# PCB_3U_CamLink.net
KiCad netlist of a schematic drawn in Altium Designer
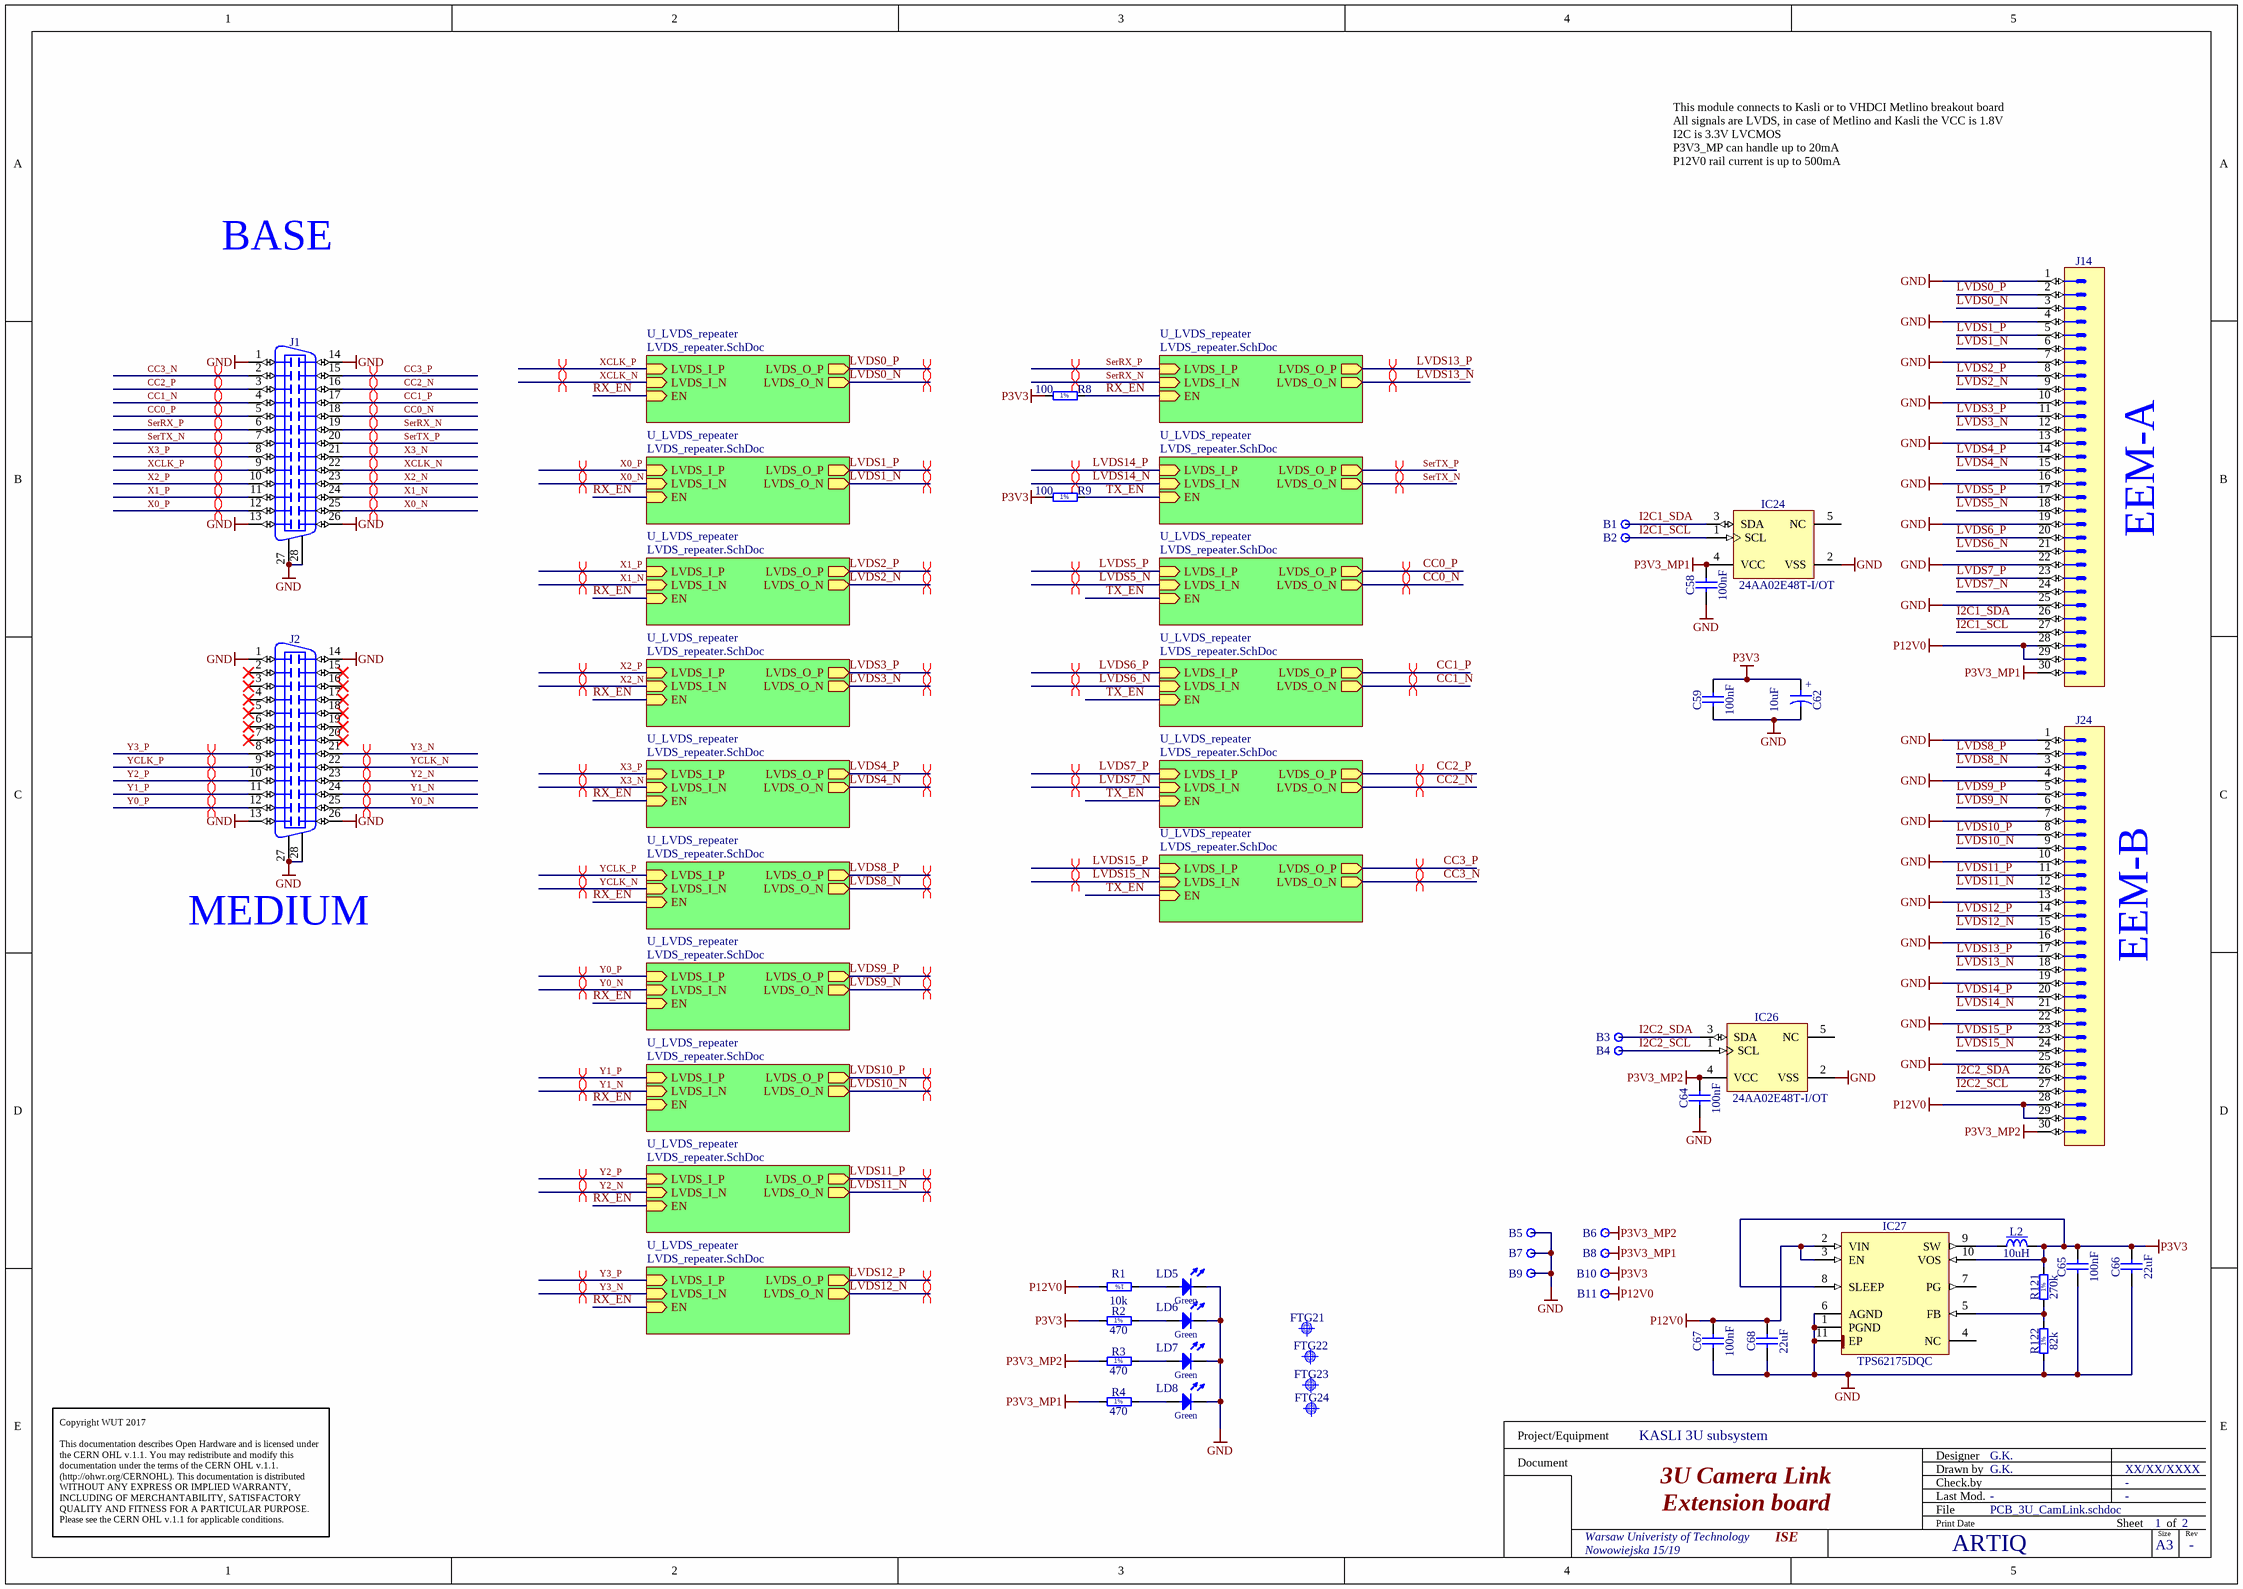
[diagram p0: PCB_3U_CamLink.schdoc]

(export (version "E")
  (design (tool "Eeschema 10.0.6"))
  (components
    (comp (ref "B1")
      (value "Plated Hole")
      (footprint "c130h60")
      (description "Single Terminal Socket")
      (fields (field (name "PART NUMBER") "PLATED_HOLE0.6_PAD1.3") (field (name "AUTHOR") "CERN DEM MR"))
      (libsource (lib "Eletro-mechanical") (part "Single Terminal Socket"))
    )
    (comp (ref "B2")
      (value "Plated Hole")
      (footprint "c130h60")
      (description "Single Terminal Socket")
      (fields (field (name "PART NUMBER") "PLATED_HOLE0.6_PAD1.3") (field (name "AUTHOR") "CERN DEM MR"))
      (libsource (lib "Eletro-mechanical") (part "Single Terminal Socket"))
    )
    (comp (ref "B3")
      (value "Plated Hole")
      (footprint "c130h60")
      (description "Single Terminal Socket")
      (fields (field (name "PART NUMBER") "PLATED_HOLE0.6_PAD1.3") (field (name "AUTHOR") "CERN DEM MR"))
      (libsource (lib "Eletro-mechanical") (part "Single Terminal Socket"))
    )
    (comp (ref "B4")
      (value "Plated Hole")
      (footprint "c130h60")
      (description "Single Terminal Socket")
      (fields (field (name "PART NUMBER") "PLATED_HOLE0.6_PAD1.3") (field (name "AUTHOR") "CERN DEM MR"))
      (libsource (lib "Eletro-mechanical") (part "Single Terminal Socket"))
    )
    (comp (ref "B5")
      (value "Plated Hole")
      (footprint "c130h60")
      (description "Single Terminal Socket")
      (fields (field (name "PART NUMBER") "PLATED_HOLE0.6_PAD1.3") (field (name "AUTHOR") "CERN DEM MR"))
      (libsource (lib "Eletro-mechanical") (part "Single Terminal Socket"))
    )
    (comp (ref "B6")
      (value "Plated Hole")
      (footprint "c130h60")
      (description "Single Terminal Socket")
      (fields (field (name "PART NUMBER") "PLATED_HOLE0.6_PAD1.3") (field (name "AUTHOR") "CERN DEM MR"))
      (libsource (lib "Eletro-mechanical") (part "Single Terminal Socket"))
    )
    (comp (ref "B7")
      (value "Plated Hole")
      (footprint "c130h60")
      (description "Single Terminal Socket")
      (fields (field (name "PART NUMBER") "PLATED_HOLE0.6_PAD1.3") (field (name "AUTHOR") "CERN DEM MR"))
      (libsource (lib "Eletro-mechanical") (part "Single Terminal Socket"))
    )
    (comp (ref "B8")
      (value "Plated Hole")
      (footprint "c130h60")
      (description "Single Terminal Socket")
      (fields (field (name "PART NUMBER") "PLATED_HOLE0.6_PAD1.3") (field (name "AUTHOR") "CERN DEM MR"))
      (libsource (lib "Eletro-mechanical") (part "Single Terminal Socket"))
    )
    (comp (ref "B9")
      (value "Plated Hole")
      (footprint "c130h60")
      (description "Single Terminal Socket")
      (fields (field (name "PART NUMBER") "PLATED_HOLE0.6_PAD1.3") (field (name "AUTHOR") "CERN DEM MR"))
      (libsource (lib "Eletro-mechanical") (part "Single Terminal Socket"))
    )
    (comp (ref "B10")
      (value "Plated Hole")
      (footprint "c130h60")
      (description "Single Terminal Socket")
      (fields (field (name "PART NUMBER") "PLATED_HOLE0.6_PAD1.3") (field (name "AUTHOR") "CERN DEM MR"))
      (libsource (lib "Eletro-mechanical") (part "Single Terminal Socket"))
    )
    (comp (ref "B11")
      (value "Plated Hole")
      (footprint "c130h60")
      (description "Single Terminal Socket")
      (fields (field (name "PART NUMBER") "PLATED_HOLE0.6_PAD1.3") (field (name "AUTHOR") "CERN DEM MR"))
      (libsource (lib "Eletro-mechanical") (part "Single Terminal Socket"))
    )
    (comp (ref "C58")
      (value "100nF")
      (footprint "CAPC1005X55N")
      (description "Non-polarised capacitor")
      (fields
        (field (name "PART NUMBER") "CC0402_100NF_16V_10%_X5R")
        (field (name "VOLTAGE") "16V")
        (field (name "AUTHOR") "CERN DEM JLC")
      )
      (libsource (lib "Capacitors") (part "Capacitor - non polarized"))
    )
    (comp (ref "C59")
      (value "100nF")
      (footprint "CAPC1005X55N")
      (description "Non-polarised capacitor")
      (fields
        (field (name "PART NUMBER") "CC0402_100NF_16V_10%_X5R")
        (field (name "VOLTAGE") "16V")
        (field (name "AUTHOR") "CERN DEM JLC")
      )
      (libsource (lib "Capacitors") (part "Capacitor - non polarized"))
    )
    (comp (ref "C62")
      (value "10uF")
      (footprint "CAPAE430X540N")
      (description "Polarised capacitor")
      (fields
        (field (name "PART NUMBER") "CAE430-540_10UF_16V_20%")
        (field (name "VOLTAGE") "16V")
        (field (name "AUTHOR") "CERN DEM JLC")
      )
      (libsource (lib "Capacitors") (part "Capacitor - polarized"))
    )
    (comp (ref "C64")
      (value "100nF")
      (footprint "CAPC1005X55N")
      (description "Non-polarised capacitor")
      (fields
        (field (name "PART NUMBER") "CC0402_100NF_16V_10%_X5R")
        (field (name "VOLTAGE") "16V")
        (field (name "AUTHOR") "CERN DEM JLC")
      )
      (libsource (lib "Capacitors") (part "Capacitor - non polarized"))
    )
    (comp (ref "C65")
      (value "100nF")
      (footprint "CAPC1005X55N")
      (description "Non-polarised capacitor")
      (fields
        (field (name "PART NUMBER") "CC0402_100NF_16V_10%_X5R")
        (field (name "VOLTAGE") "16V")
        (field (name "AUTHOR") "CERN DEM JLC")
      )
      (libsource (lib "Capacitors") (part "Capacitor - non polarized"))
    )
    (comp (ref "C66")
      (value "22uF")
      (footprint "CAPC2012X135N")
      (description "Non-polarised capacitor")
      (fields
        (field (name "PART NUMBER") "CC0805_22UF_16V_10%_X5R")
        (field (name "VOLTAGE") "16V")
        (field (name "AUTHOR") "CERN DEM JLC")
      )
      (libsource (lib "Capacitors") (part "Capacitor - non polarized"))
    )
    (comp (ref "C67")
      (value "100nF")
      (footprint "CAPC1005X55N")
      (description "Non-polarised capacitor")
      (fields
        (field (name "PART NUMBER") "CC0402_100NF_16V_10%_X5R")
        (field (name "VOLTAGE") "16V")
        (field (name "AUTHOR") "CERN DEM JLC")
      )
      (libsource (lib "Capacitors") (part "Capacitor - non polarized"))
    )
    (comp (ref "C68")
      (value "22uF")
      (footprint "CAPC2012X135N")
      (description "Non-polarised capacitor")
      (fields
        (field (name "PART NUMBER") "CC0805_22UF_16V_10%_X5R")
        (field (name "VOLTAGE") "16V")
        (field (name "AUTHOR") "CERN DEM JLC")
      )
      (libsource (lib "Capacitors") (part "Capacitor - non polarized"))
    )
    (comp (ref "FTG21")
      (value "Use only in PCB")
      (footprint "FIDUCIAL_TOP_C100-200")
      (description "Fiducial Target")
      (fields (field (name "PART NUMBER") "FIDUCIAL_TARGET_C100-200") (field (name "AUTHOR") "CERN DEM JLC"))
      (libsource (lib "Eletro-mechanical") (part "Fiducial Target"))
    )
    (comp (ref "FTG22")
      (value "Use only in PCB")
      (footprint "FIDUCIAL_TOP_S100-200")
      (description "Fiducial Target")
      (fields (field (name "PART NUMBER") "FIDUCIAL_TARGET_S100-200") (field (name "AUTHOR") "CERN DEM JLC"))
      (libsource (lib "Eletro-mechanical") (part "Fiducial Target"))
    )
    (comp (ref "FTG23")
      (value "Use only in PCB")
      (footprint "FIDUCIAL_TOP_S200-400")
      (description "Fiducial Target")
      (fields (field (name "PART NUMBER") "FIDUCIAL_TARGET_S200-400") (field (name "AUTHOR") "CERN DEM JLC"))
      (libsource (lib "Eletro-mechanical") (part "Fiducial Target"))
    )
    (comp (ref "FTG24")
      (value "Use only in PCB")
      (footprint "FIDUCIAL_TOP_S100-200")
      (description "Fiducial Target")
      (fields (field (name "PART NUMBER") "FIDUCIAL_TARGET_S100-200") (field (name "AUTHOR") "CERN DEM JLC"))
      (libsource (lib "Eletro-mechanical") (part "Fiducial Target"))
    )
    (comp (ref "IC24")
      (value "24AA02E48T-I/OT")
      (footprint "SOT95P280X145-5N")
      (description "1.7V-5.5V, 2K I2C Serial EEPROM With EUI-48 Node Identity")
      (fields (field (name "MANUFACTURER") "MICROCHIP TECHNOLOGY") (field (name "AUTHOR") "CERN DEM MR"))
      (libsource (lib "ICs And Semiconductors") (part "24AA02E48T-I/OT"))
    )
    (comp (ref "IC26")
      (value "24AA02E48T-I/OT")
      (footprint "SOT95P280X145-5N")
      (description "1.7V-5.5V, 2K I2C Serial EEPROM With EUI-48 Node Identity")
      (fields (field (name "MANUFACTURER") "MICROCHIP TECHNOLOGY") (field (name "AUTHOR") "CERN DEM MR"))
      (libsource (lib "ICs And Semiconductors") (part "24AA02E48T-I/OT"))
    )
    (comp (ref "IC27")
      (value "TPS62175DQC")
      (footprint "SON50P200X300X80-11N-R94X250")
      (description "4.75-28VDC to 1-6VDC, 500mA Step-Down Converter With Sleep Mode")
      (fields (field (name "MANUFACTURER") "TEXAS INSTRUMENTS") (field (name "AUTHOR") "CERN DEM JMW"))
      (libsource (lib "ICs And Semiconductors") (part "TPS62175"))
    )
    (comp (ref "J1")
      (value "MDR 26")
      (footprint "3M_N10226-5212PC")
      (description "Connector Mini D Ribbon (MDR) 26 Female")
      (fields
        (field (name "PART NUMBER") "3M_N10226-5212PC")
        (field (name "MANUFACTURER") "3M")
        (field (name "AUTHOR") "CERN DEM JLC")
      )
      (libsource (lib "Connectors") (part "Connector MDR 26 Female"))
    )
    (comp (ref "J2")
      (value "MDR 26")
      (footprint "3M_N10226-5212PC")
      (description "Connector Mini D Ribbon (MDR) 26 Female")
      (fields
        (field (name "PART NUMBER") "3M_N10226-5212PC")
        (field (name "MANUFACTURER") "3M")
        (field (name "AUTHOR") "CERN DEM JLC")
      )
      (libsource (lib "Connectors") (part "Connector MDR 26 Female"))
    )
    (comp (ref "J14")
      (value "~")
      (footprint "3M_N2530-6002RB")
      (description "Connector 30 Male")
      (fields
        (field (name "PART NUMBER") "3M_N2530-6002RB")
        (field (name "MANUFACTURER") "3M")
        (field (name "AUTHOR") "CERN DEM JLC")
      )
      (libsource (lib "Connectors") (part "Connector 30 Male"))
    )
    (comp (ref "J24")
      (value "~")
      (footprint "3M_N2530-6002RB")
      (description "Connector 30 Male")
      (fields
        (field (name "PART NUMBER") "3M_N2530-6002RB")
        (field (name "MANUFACTURER") "3M")
        (field (name "AUTHOR") "CERN DEM JLC")
      )
      (libsource (lib "Connectors") (part "Connector 30 Male"))
    )
    (comp (ref "L2")
      (value "10uH")
      (footprint "IND_MURATA-PS_8400")
      (description "Inductor With Core")
      (fields
        (field (name "PART NUMBER") "IND_10UH_10%_MURATA-PS_8400")
        (field (name "POWER") "950mA")
        (field (name "AUTHOR") "CERN DEM JLC")
      )
      (libsource (lib "Inductors & Transformers") (part "Inductor With Magnetic core"))
    )
    (comp (ref "LD5")
      (value "Green")
      (footprint "LED_KINGBRIGHT_KPH-1608CGCK")
      (description "LED Green 1C 2A")
      (fields
        (field (name "PART NUMBER") "LED_KINGBRIGHT_KPH-1608CGCK")
        (field (name "MANUFACTURER") "KINGBRIGHT")
        (field (name "AUTHOR") "CERN DEM JLC")
      )
      (libsource (lib "ICs And Semiconductors") (part "LED Green 1C 2A"))
    )
    (comp (ref "LD6")
      (value "Green")
      (footprint "LED_KINGBRIGHT_KPH-1608CGCK")
      (description "LED Green 1C 2A")
      (fields
        (field (name "PART NUMBER") "LED_KINGBRIGHT_KPH-1608CGCK")
        (field (name "MANUFACTURER") "KINGBRIGHT")
        (field (name "AUTHOR") "CERN DEM JLC")
      )
      (libsource (lib "ICs And Semiconductors") (part "LED Green 1C 2A"))
    )
    (comp (ref "LD7")
      (value "Green")
      (footprint "LED_KINGBRIGHT_KPH-1608CGCK")
      (description "LED Green 1C 2A")
      (fields
        (field (name "PART NUMBER") "LED_KINGBRIGHT_KPH-1608CGCK")
        (field (name "MANUFACTURER") "KINGBRIGHT")
        (field (name "AUTHOR") "CERN DEM JLC")
      )
      (libsource (lib "ICs And Semiconductors") (part "LED Green 1C 2A"))
    )
    (comp (ref "LD8")
      (value "Green")
      (footprint "LED_KINGBRIGHT_KPH-1608CGCK")
      (description "LED Green 1C 2A")
      (fields
        (field (name "PART NUMBER") "LED_KINGBRIGHT_KPH-1608CGCK")
        (field (name "MANUFACTURER") "KINGBRIGHT")
        (field (name "AUTHOR") "CERN DEM JLC")
      )
      (libsource (lib "ICs And Semiconductors") (part "LED Green 1C 2A"))
    )
    (comp (ref "R1")
      (value "10k")
      (footprint "RESC1005X40N")
      (description "Resistor - 1%")
      (fields
        (field (name "PART NUMBER") "R0402_10K_1%_0.0625W_100PPM")
        (field (name "POWER") "0.0625W")
        (field (name "AUTHOR") "CERN DEM JLC")
      )
      (libsource (lib "Resistors") (part "Resistor - 1%"))
    )
    (comp (ref "R2")
      (value "470")
      (footprint "RESC1005X40N")
      (description "Resistor - 1%")
      (fields
        (field (name "PART NUMBER") "R0402_470R_1%_0.0625W_100PPM")
        (field (name "POWER") "0.0625W")
        (field (name "AUTHOR") "CERN DEM JLC")
      )
      (libsource (lib "Resistors") (part "Resistor - 1%"))
    )
    (comp (ref "R3")
      (value "470")
      (footprint "RESC1005X40N")
      (description "Resistor - 1%")
      (fields
        (field (name "PART NUMBER") "R0402_470R_1%_0.0625W_100PPM")
        (field (name "POWER") "0.0625W")
        (field (name "AUTHOR") "CERN DEM JLC")
      )
      (libsource (lib "Resistors") (part "Resistor - 1%"))
    )
    (comp (ref "R4")
      (value "470")
      (footprint "RESC1005X40N")
      (description "Resistor - 1%")
      (fields
        (field (name "PART NUMBER") "R0402_470R_1%_0.0625W_100PPM")
        (field (name "POWER") "0.0625W")
        (field (name "AUTHOR") "CERN DEM JLC")
      )
      (libsource (lib "Resistors") (part "Resistor - 1%"))
    )
    (comp (ref "R8")
      (value "100")
      (footprint "RESC1005X40N")
      (description "Resistor - 1%")
      (fields
        (field (name "PART NUMBER") "R0402_100R_1%_0.1W_100PPM")
        (field (name "POWER") "0.1W")
        (field (name "AUTHOR") "CERN DEM JLC")
      )
      (libsource (lib "Resistors") (part "Resistor - 1%"))
    )
    (comp (ref "R9")
      (value "100")
      (footprint "RESC1005X40N")
      (description "Resistor - 1%")
      (fields
        (field (name "PART NUMBER") "R0402_100R_1%_0.1W_100PPM")
        (field (name "POWER") "0.1W")
        (field (name "AUTHOR") "CERN DEM JLC")
      )
      (libsource (lib "Resistors") (part "Resistor - 1%"))
    )
    (comp (ref "R121")
      (value "270k")
      (footprint "RESC1608X55N")
      (description "Resistor - 1%")
      (fields
        (field (name "PART NUMBER") "R0603_270K_1%_0.1W_100PPM")
        (field (name "POWER") "0.1W")
        (field (name "AUTHOR") "CERN DEM JLC")
      )
      (libsource (lib "Resistors") (part "Resistor - 1%"))
    )
    (comp (ref "R122")
      (value "82k")
      (footprint "RESC1608X55N")
      (description "Resistor - 1%")
      (fields
        (field (name "PART NUMBER") "R0603_82K_1%_0.1W_100PPM")
        (field (name "POWER") "0.1W")
        (field (name "AUTHOR") "CERN DEM JLC")
      )
      (libsource (lib "Resistors") (part "Resistor - 1%"))
    )
  )
  (nets
    (net (code "1") (name "/CC0_N") (class "Default")
      (node (ref "J1") (pin "18") (pinfunction "18_18") (pintype "bidirectional"))
    )
    (net (code "2") (name "/CC0_P") (class "Default")
      (node (ref "J1") (pin "5") (pinfunction "5_5") (pintype "bidirectional"))
    )
    (net (code "3") (name "/CC1_N") (class "Default")
      (node (ref "J1") (pin "4") (pinfunction "4_4") (pintype "bidirectional"))
    )
    (net (code "4") (name "/CC1_P") (class "Default")
      (node (ref "J1") (pin "17") (pinfunction "17_17") (pintype "bidirectional"))
    )
    (net (code "5") (name "/CC2_N") (class "Default")
      (node (ref "J1") (pin "16") (pinfunction "16_16") (pintype "bidirectional"))
    )
    (net (code "6") (name "/CC2_P") (class "Default")
      (node (ref "J1") (pin "3") (pinfunction "3_3") (pintype "bidirectional"))
    )
    (net (code "7") (name "/CC3_N") (class "Default")
      (node (ref "J1") (pin "2") (pinfunction "2_2") (pintype "bidirectional"))
    )
    (net (code "8") (name "/CC3_P") (class "Default")
      (node (ref "J1") (pin "15") (pinfunction "15_15") (pintype "bidirectional"))
    )
    (net (code "9") (name "/I2C1_SCL") (class "Default")
      (node (ref "B2") (pin "1") (pinfunction "1_1") (pintype "bidirectional"))
      (node (ref "IC24") (pin "1") (pinfunction "SCL_1") (pintype "input"))
      (node (ref "J14") (pin "27") (pinfunction "27_27") (pintype "bidirectional"))
    )
    (net (code "10") (name "/I2C1_SDA") (class "Default")
      (node (ref "B1") (pin "1") (pinfunction "1_1") (pintype "bidirectional"))
      (node (ref "IC24") (pin "3") (pinfunction "SDA_3") (pintype "bidirectional"))
      (node (ref "J14") (pin "26") (pinfunction "26_26") (pintype "bidirectional"))
    )
    (net (code "11") (name "/I2C2_SCL") (class "Default")
      (node (ref "B4") (pin "1") (pinfunction "1_1") (pintype "bidirectional"))
      (node (ref "IC26") (pin "1") (pinfunction "SCL_1") (pintype "input"))
      (node (ref "J24") (pin "27") (pinfunction "27_27") (pintype "bidirectional"))
    )
    (net (code "12") (name "/I2C2_SDA") (class "Default")
      (node (ref "B3") (pin "1") (pinfunction "1_1") (pintype "bidirectional"))
      (node (ref "IC26") (pin "3") (pinfunction "SDA_3") (pintype "bidirectional"))
      (node (ref "J24") (pin "26") (pinfunction "26_26") (pintype "bidirectional"))
    )
    (net (code "13") (name "/LVDS0_N") (class "Default")
      (node (ref "J14") (pin "3") (pinfunction "3_3") (pintype "bidirectional"))
    )
    (net (code "14") (name "/LVDS0_P") (class "Default")
      (node (ref "J14") (pin "2") (pinfunction "2_2") (pintype "bidirectional"))
    )
    (net (code "15") (name "/LVDS1_N") (class "Default")
      (node (ref "J14") (pin "6") (pinfunction "6_6") (pintype "bidirectional"))
    )
    (net (code "16") (name "/LVDS1_P") (class "Default")
      (node (ref "J14") (pin "5") (pinfunction "5_5") (pintype "bidirectional"))
    )
    (net (code "17") (name "/LVDS2_N") (class "Default")
      (node (ref "J14") (pin "9") (pinfunction "9_9") (pintype "bidirectional"))
    )
    (net (code "18") (name "/LVDS2_P") (class "Default")
      (node (ref "J14") (pin "8") (pinfunction "8_8") (pintype "bidirectional"))
    )
    (net (code "19") (name "/LVDS3_N") (class "Default")
      (node (ref "J14") (pin "12") (pinfunction "12_12") (pintype "bidirectional"))
    )
    (net (code "20") (name "/LVDS3_P") (class "Default")
      (node (ref "J14") (pin "11") (pinfunction "11_11") (pintype "bidirectional"))
    )
    (net (code "21") (name "/LVDS4_N") (class "Default")
      (node (ref "J14") (pin "15") (pinfunction "15_15") (pintype "bidirectional"))
    )
    (net (code "22") (name "/LVDS4_P") (class "Default")
      (node (ref "J14") (pin "14") (pinfunction "14_14") (pintype "bidirectional"))
    )
    (net (code "23") (name "/LVDS5_N") (class "Default")
      (node (ref "J14") (pin "18") (pinfunction "18_18") (pintype "bidirectional"))
    )
    (net (code "24") (name "/LVDS5_P") (class "Default")
      (node (ref "J14") (pin "17") (pinfunction "17_17") (pintype "bidirectional"))
    )
    (net (code "25") (name "/LVDS6_N") (class "Default")
      (node (ref "J14") (pin "21") (pinfunction "21_21") (pintype "bidirectional"))
    )
    (net (code "26") (name "/LVDS6_P") (class "Default")
      (node (ref "J14") (pin "20") (pinfunction "20_20") (pintype "bidirectional"))
    )
    (net (code "27") (name "/LVDS7_N") (class "Default")
      (node (ref "J14") (pin "24") (pinfunction "24_24") (pintype "bidirectional"))
    )
    (net (code "28") (name "/LVDS7_P") (class "Default")
      (node (ref "J14") (pin "23") (pinfunction "23_23") (pintype "bidirectional"))
    )
    (net (code "29") (name "/LVDS8_N") (class "Default")
      (node (ref "J24") (pin "3") (pinfunction "3_3") (pintype "bidirectional"))
    )
    (net (code "30") (name "/LVDS8_P") (class "Default")
      (node (ref "J24") (pin "2") (pinfunction "2_2") (pintype "bidirectional"))
    )
    (net (code "31") (name "/LVDS9_N") (class "Default")
      (node (ref "J24") (pin "6") (pinfunction "6_6") (pintype "bidirectional"))
    )
    (net (code "32") (name "/LVDS9_P") (class "Default")
      (node (ref "J24") (pin "5") (pinfunction "5_5") (pintype "bidirectional"))
    )
    (net (code "33") (name "/LVDS10_N") (class "Default")
      (node (ref "J24") (pin "9") (pinfunction "9_9") (pintype "bidirectional"))
    )
    (net (code "34") (name "/LVDS10_P") (class "Default")
      (node (ref "J24") (pin "8") (pinfunction "8_8") (pintype "bidirectional"))
    )
    (net (code "35") (name "/LVDS11_N") (class "Default")
      (node (ref "J24") (pin "12") (pinfunction "12_12") (pintype "bidirectional"))
    )
    (net (code "36") (name "/LVDS11_P") (class "Default")
      (node (ref "J24") (pin "11") (pinfunction "11_11") (pintype "bidirectional"))
    )
    (net (code "37") (name "/LVDS12_N") (class "Default")
      (node (ref "J24") (pin "15") (pinfunction "15_15") (pintype "bidirectional"))
    )
    (net (code "38") (name "/LVDS12_P") (class "Default")
      (node (ref "J24") (pin "14") (pinfunction "14_14") (pintype "bidirectional"))
    )
    (net (code "39") (name "/LVDS13_N") (class "Default")
      (node (ref "J24") (pin "18") (pinfunction "18_18") (pintype "bidirectional"))
    )
    (net (code "40") (name "/LVDS13_P") (class "Default")
      (node (ref "J24") (pin "17") (pinfunction "17_17") (pintype "bidirectional"))
    )
    (net (code "41") (name "/LVDS14_N") (class "Default")
      (node (ref "J24") (pin "21") (pinfunction "21_21") (pintype "bidirectional"))
    )
    (net (code "42") (name "/LVDS14_P") (class "Default")
      (node (ref "J24") (pin "20") (pinfunction "20_20") (pintype "bidirectional"))
    )
    (net (code "43") (name "/LVDS15_N") (class "Default")
      (node (ref "J24") (pin "24") (pinfunction "24_24") (pintype "bidirectional"))
    )
    (net (code "44") (name "/LVDS15_P") (class "Default")
      (node (ref "J24") (pin "23") (pinfunction "23_23") (pintype "bidirectional"))
    )
    (net (code "45") (name "/RX_EN") (class "Default")
      (node (ref "R8") (pin "2") (pinfunction "2_2") (pintype "passive"))
    )
    (net (code "46") (name "/SerRX_N") (class "Default")
      (node (ref "J1") (pin "19") (pinfunction "19_19") (pintype "bidirectional"))
    )
    (net (code "47") (name "/SerRX_P") (class "Default")
      (node (ref "J1") (pin "6") (pinfunction "6_6") (pintype "bidirectional"))
    )
    (net (code "48") (name "/SerTX_N") (class "Default")
      (node (ref "J1") (pin "7") (pinfunction "7_7") (pintype "bidirectional"))
    )
    (net (code "49") (name "/SerTX_P") (class "Default")
      (node (ref "J1") (pin "20") (pinfunction "20_20") (pintype "bidirectional"))
    )
    (net (code "50") (name "/TX_EN") (class "Default")
      (node (ref "R9") (pin "2") (pinfunction "2_2") (pintype "passive"))
    )
    (net (code "51") (name "/X0_N") (class "Default")
      (node (ref "J1") (pin "25") (pinfunction "25_25") (pintype "bidirectional"))
    )
    (net (code "52") (name "/X0_P") (class "Default")
      (node (ref "J1") (pin "12") (pinfunction "12_12") (pintype "bidirectional"))
    )
    (net (code "53") (name "/X1_N") (class "Default")
      (node (ref "J1") (pin "24") (pinfunction "24_24") (pintype "bidirectional"))
    )
    (net (code "54") (name "/X1_P") (class "Default")
      (node (ref "J1") (pin "11") (pinfunction "11_11") (pintype "bidirectional"))
    )
    (net (code "55") (name "/X2_N") (class "Default")
      (node (ref "J1") (pin "23") (pinfunction "23_23") (pintype "bidirectional"))
    )
    (net (code "56") (name "/X2_P") (class "Default")
      (node (ref "J1") (pin "10") (pinfunction "10_10") (pintype "bidirectional"))
    )
    (net (code "57") (name "/X3_N") (class "Default")
      (node (ref "J1") (pin "21") (pinfunction "21_21") (pintype "bidirectional"))
    )
    (net (code "58") (name "/X3_P") (class "Default")
      (node (ref "J1") (pin "8") (pinfunction "8_8") (pintype "bidirectional"))
    )
    (net (code "59") (name "/XCLK_N") (class "Default")
      (node (ref "J1") (pin "22") (pinfunction "22_22") (pintype "bidirectional"))
    )
    (net (code "60") (name "/XCLK_P") (class "Default")
      (node (ref "J1") (pin "9") (pinfunction "9_9") (pintype "bidirectional"))
    )
    (net (code "61") (name "/Y0_N") (class "Default")
      (node (ref "J2") (pin "25") (pinfunction "25_25") (pintype "bidirectional"))
    )
    (net (code "62") (name "/Y0_P") (class "Default")
      (node (ref "J2") (pin "12") (pinfunction "12_12") (pintype "bidirectional"))
    )
    (net (code "63") (name "/Y1_N") (class "Default")
      (node (ref "J2") (pin "24") (pinfunction "24_24") (pintype "bidirectional"))
    )
    (net (code "64") (name "/Y1_P") (class "Default")
      (node (ref "J2") (pin "11") (pinfunction "11_11") (pintype "bidirectional"))
    )
    (net (code "65") (name "/Y2_N") (class "Default")
      (node (ref "J2") (pin "23") (pinfunction "23_23") (pintype "bidirectional"))
    )
    (net (code "66") (name "/Y2_P") (class "Default")
      (node (ref "J2") (pin "10") (pinfunction "10_10") (pintype "bidirectional"))
    )
    (net (code "67") (name "/Y3_N") (class "Default")
      (node (ref "J2") (pin "21") (pinfunction "21_21") (pintype "bidirectional"))
    )
    (net (code "68") (name "/Y3_P") (class "Default")
      (node (ref "J2") (pin "8") (pinfunction "8_8") (pintype "bidirectional"))
    )
    (net (code "69") (name "/YCLK_N") (class "Default")
      (node (ref "J2") (pin "22") (pinfunction "22_22") (pintype "bidirectional"))
    )
    (net (code "70") (name "/YCLK_P") (class "Default")
      (node (ref "J2") (pin "9") (pinfunction "9_9") (pintype "bidirectional"))
    )
    (net (code "71") (name "GND") (class "Default")
      (node (ref "B5") (pin "1") (pinfunction "1_1") (pintype "bidirectional"))
      (node (ref "B7") (pin "1") (pinfunction "1_1") (pintype "bidirectional"))
      (node (ref "B9") (pin "1") (pinfunction "1_1") (pintype "bidirectional"))
      (node (ref "C58") (pin "1") (pinfunction "1_1") (pintype "passive"))
      (node (ref "C59") (pin "1") (pinfunction "1_1") (pintype "passive"))
      (node (ref "C62") (pin "2") (pinfunction "2_2") (pintype "passive"))
      (node (ref "C64") (pin "1") (pinfunction "1_1") (pintype "passive"))
      (node (ref "C65") (pin "1") (pinfunction "1_1") (pintype "passive"))
      (node (ref "C66") (pin "1") (pinfunction "1_1") (pintype "passive"))
      (node (ref "C67") (pin "1") (pinfunction "1_1") (pintype "passive"))
      (node (ref "C68") (pin "1") (pinfunction "1_1") (pintype "passive"))
      (node (ref "IC24") (pin "2") (pinfunction "VSS_2") (pintype "power_in"))
      (node (ref "IC26") (pin "2") (pinfunction "VSS_2") (pintype "power_in"))
      (node (ref "IC27") (pin "1") (pinfunction "PGND_1") (pintype "power_in"))
      (node (ref "IC27") (pin "11") (pinfunction "EP_11") (pintype "power_in"))
      (node (ref "IC27") (pin "6") (pinfunction "AGND_6") (pintype "power_in"))
      (node (ref "J1") (pin "1") (pinfunction "1_1") (pintype "bidirectional"))
      (node (ref "J1") (pin "13") (pinfunction "13_13") (pintype "bidirectional"))
      (node (ref "J1") (pin "14") (pinfunction "14_14") (pintype "bidirectional"))
      (node (ref "J1") (pin "26") (pinfunction "26_26") (pintype "bidirectional"))
      (node (ref "J1") (pin "27") (pinfunction "27_27") (pintype "passive"))
      (node (ref "J1") (pin "28") (pinfunction "28_28") (pintype "passive"))
      (node (ref "J14") (pin "1") (pinfunction "1_1") (pintype "bidirectional"))
      (node (ref "J14") (pin "10") (pinfunction "10_10") (pintype "bidirectional"))
      (node (ref "J14") (pin "13") (pinfunction "13_13") (pintype "bidirectional"))
      (node (ref "J14") (pin "16") (pinfunction "16_16") (pintype "bidirectional"))
      (node (ref "J14") (pin "19") (pinfunction "19_19") (pintype "bidirectional"))
      (node (ref "J14") (pin "22") (pinfunction "22_22") (pintype "bidirectional"))
      (node (ref "J14") (pin "25") (pinfunction "25_25") (pintype "bidirectional"))
      (node (ref "J14") (pin "4") (pinfunction "4_4") (pintype "bidirectional"))
      (node (ref "J14") (pin "7") (pinfunction "7_7") (pintype "bidirectional"))
      (node (ref "J2") (pin "1") (pinfunction "1_1") (pintype "bidirectional"))
      (node (ref "J2") (pin "13") (pinfunction "13_13") (pintype "bidirectional"))
      (node (ref "J2") (pin "14") (pinfunction "14_14") (pintype "bidirectional"))
      (node (ref "J2") (pin "26") (pinfunction "26_26") (pintype "bidirectional"))
      (node (ref "J2") (pin "27") (pinfunction "27_27") (pintype "passive"))
      (node (ref "J2") (pin "28") (pinfunction "28_28") (pintype "passive"))
      (node (ref "J24") (pin "1") (pinfunction "1_1") (pintype "bidirectional"))
      (node (ref "J24") (pin "10") (pinfunction "10_10") (pintype "bidirectional"))
      (node (ref "J24") (pin "13") (pinfunction "13_13") (pintype "bidirectional"))
      (node (ref "J24") (pin "16") (pinfunction "16_16") (pintype "bidirectional"))
      (node (ref "J24") (pin "19") (pinfunction "19_19") (pintype "bidirectional"))
      (node (ref "J24") (pin "22") (pinfunction "22_22") (pintype "bidirectional"))
      (node (ref "J24") (pin "25") (pinfunction "25_25") (pintype "bidirectional"))
      (node (ref "J24") (pin "4") (pinfunction "4_4") (pintype "bidirectional"))
      (node (ref "J24") (pin "7") (pinfunction "7_7") (pintype "bidirectional"))
      (node (ref "LD5") (pin "1") (pinfunction "C_1") (pintype "passive"))
      (node (ref "LD6") (pin "1") (pinfunction "C_1") (pintype "passive"))
      (node (ref "LD7") (pin "1") (pinfunction "C_1") (pintype "passive"))
      (node (ref "LD8") (pin "1") (pinfunction "C_1") (pintype "passive"))
      (node (ref "R122") (pin "1") (pinfunction "1_1") (pintype "passive"))
    )
    (net (code "72") (name "Net-(IC27-FB)") (class "Default")
      (node (ref "IC27") (pin "5") (pinfunction "FB_5") (pintype "input"))
      (node (ref "R121") (pin "1") (pinfunction "1_1") (pintype "passive"))
      (node (ref "R122") (pin "2") (pinfunction "2_2") (pintype "passive"))
    )
    (net (code "73") (name "Net-(IC27-SW)") (class "Default")
      (node (ref "IC27") (pin "9") (pinfunction "SW_9") (pintype "output"))
      (node (ref "L2") (pin "1") (pinfunction "1_1") (pintype "passive"))
    )
    (net (code "74") (name "Net-(LD5-A)") (class "Default")
      (node (ref "LD5") (pin "2") (pinfunction "A_2") (pintype "passive"))
      (node (ref "R1") (pin "1") (pinfunction "1_1") (pintype "passive"))
    )
    (net (code "75") (name "Net-(LD6-A)") (class "Default")
      (node (ref "LD6") (pin "2") (pinfunction "A_2") (pintype "passive"))
      (node (ref "R2") (pin "2") (pinfunction "2_2") (pintype "passive"))
    )
    (net (code "76") (name "Net-(LD7-A)") (class "Default")
      (node (ref "LD7") (pin "2") (pinfunction "A_2") (pintype "passive"))
      (node (ref "R3") (pin "2") (pinfunction "2_2") (pintype "passive"))
    )
    (net (code "77") (name "Net-(LD8-A)") (class "Default")
      (node (ref "LD8") (pin "2") (pinfunction "A_2") (pintype "passive"))
      (node (ref "R4") (pin "2") (pinfunction "2_2") (pintype "passive"))
    )
    (net (code "78") (name "P3V3") (class "Default")
      (node (ref "B10") (pin "1") (pinfunction "1_1") (pintype "bidirectional"))
      (node (ref "C59") (pin "2") (pinfunction "2_2") (pintype "passive"))
      (node (ref "C62") (pin "1") (pinfunction "1_1") (pintype "passive"))
      (node (ref "C65") (pin "2") (pinfunction "2_2") (pintype "passive"))
      (node (ref "C66") (pin "2") (pinfunction "2_2") (pintype "passive"))
      (node (ref "IC27") (pin "10") (pinfunction "VOS_10") (pintype "input"))
      (node (ref "IC27") (pin "8") (pinfunction "SLEEP_8") (pintype "input"))
      (node (ref "L2") (pin "2") (pinfunction "2_2") (pintype "passive"))
      (node (ref "R121") (pin "2") (pinfunction "2_2") (pintype "passive"))
      (node (ref "R2") (pin "1") (pinfunction "1_1") (pintype "passive"))
      (node (ref "R8") (pin "1") (pinfunction "1_1") (pintype "passive"))
      (node (ref "R9") (pin "1") (pinfunction "1_1") (pintype "passive"))
    )
    (net (code "79") (name "P3V3_MP1") (class "Default")
      (node (ref "B8") (pin "1") (pinfunction "1_1") (pintype "bidirectional"))
      (node (ref "C58") (pin "2") (pinfunction "2_2") (pintype "passive"))
      (node (ref "IC24") (pin "4") (pinfunction "VCC_4") (pintype "power_in"))
      (node (ref "J14") (pin "30") (pinfunction "30_30") (pintype "bidirectional"))
      (node (ref "R4") (pin "1") (pinfunction "1_1") (pintype "passive"))
    )
    (net (code "80") (name "P3V3_MP2") (class "Default")
      (node (ref "B6") (pin "1") (pinfunction "1_1") (pintype "bidirectional"))
      (node (ref "C64") (pin "2") (pinfunction "2_2") (pintype "passive"))
      (node (ref "IC26") (pin "4") (pinfunction "VCC_4") (pintype "power_in"))
      (node (ref "J24") (pin "30") (pinfunction "30_30") (pintype "bidirectional"))
      (node (ref "R3") (pin "1") (pinfunction "1_1") (pintype "passive"))
    )
    (net (code "81") (name "P12V0") (class "Default")
      (node (ref "B11") (pin "1") (pinfunction "1_1") (pintype "bidirectional"))
      (node (ref "C67") (pin "2") (pinfunction "2_2") (pintype "passive"))
      (node (ref "C68") (pin "2") (pinfunction "2_2") (pintype "passive"))
      (node (ref "IC27") (pin "2") (pinfunction "VIN_2") (pintype "input"))
      (node (ref "IC27") (pin "3") (pinfunction "EN_3") (pintype "input"))
      (node (ref "J14") (pin "28") (pinfunction "28_28") (pintype "bidirectional"))
      (node (ref "J14") (pin "29") (pinfunction "29_29") (pintype "bidirectional"))
      (node (ref "J24") (pin "28") (pinfunction "28_28") (pintype "bidirectional"))
      (node (ref "J24") (pin "29") (pinfunction "29_29") (pintype "bidirectional"))
      (node (ref "R1") (pin "2") (pinfunction "2_2") (pintype "passive"))
    )
    (net (code "82") (name "unconnected-(IC24-NC-Pad5)") (class "Default")
      (node (ref "IC24") (pin "5") (pinfunction "NC_5") (pintype "passive"))
    )
    (net (code "83") (name "unconnected-(IC26-NC-Pad5)") (class "Default")
      (node (ref "IC26") (pin "5") (pinfunction "NC_5") (pintype "passive"))
    )
    (net (code "84") (name "unconnected-(IC27-NC-Pad4)") (class "Default")
      (node (ref "IC27") (pin "4") (pinfunction "NC_4") (pintype "passive"))
    )
    (net (code "85") (name "unconnected-(IC27-PG-Pad7)") (class "Default")
      (node (ref "IC27") (pin "7") (pinfunction "PG_7") (pintype "output"))
    )
    (net (code "86") (name "unconnected-(J2-Pad2)") (class "Default")
      (node (ref "J2") (pin "2") (pinfunction "2_2") (pintype "bidirectional+no_connect"))
    )
    (net (code "87") (name "unconnected-(J2-Pad3)") (class "Default")
      (node (ref "J2") (pin "3") (pinfunction "3_3") (pintype "bidirectional+no_connect"))
    )
    (net (code "88") (name "unconnected-(J2-Pad4)") (class "Default")
      (node (ref "J2") (pin "4") (pinfunction "4_4") (pintype "bidirectional+no_connect"))
    )
    (net (code "89") (name "unconnected-(J2-Pad5)") (class "Default")
      (node (ref "J2") (pin "5") (pinfunction "5_5") (pintype "bidirectional+no_connect"))
    )
    (net (code "90") (name "unconnected-(J2-Pad6)") (class "Default")
      (node (ref "J2") (pin "6") (pinfunction "6_6") (pintype "bidirectional+no_connect"))
    )
    (net (code "91") (name "unconnected-(J2-Pad7)") (class "Default")
      (node (ref "J2") (pin "7") (pinfunction "7_7") (pintype "bidirectional+no_connect"))
    )
    (net (code "92") (name "unconnected-(J2-Pad15)") (class "Default")
      (node (ref "J2") (pin "15") (pinfunction "15_15") (pintype "bidirectional+no_connect"))
    )
    (net (code "93") (name "unconnected-(J2-Pad16)") (class "Default")
      (node (ref "J2") (pin "16") (pinfunction "16_16") (pintype "bidirectional+no_connect"))
    )
    (net (code "94") (name "unconnected-(J2-Pad17)") (class "Default")
      (node (ref "J2") (pin "17") (pinfunction "17_17") (pintype "bidirectional+no_connect"))
    )
    (net (code "95") (name "unconnected-(J2-Pad18)") (class "Default")
      (node (ref "J2") (pin "18") (pinfunction "18_18") (pintype "bidirectional+no_connect"))
    )
    (net (code "96") (name "unconnected-(J2-Pad19)") (class "Default")
      (node (ref "J2") (pin "19") (pinfunction "19_19") (pintype "bidirectional+no_connect"))
    )
    (net (code "97") (name "unconnected-(J2-Pad20)") (class "Default")
      (node (ref "J2") (pin "20") (pinfunction "20_20") (pintype "bidirectional+no_connect"))
    )
  )
)
